# MCU.net
KiCad netlist of a schematic drawn in Altium Designer
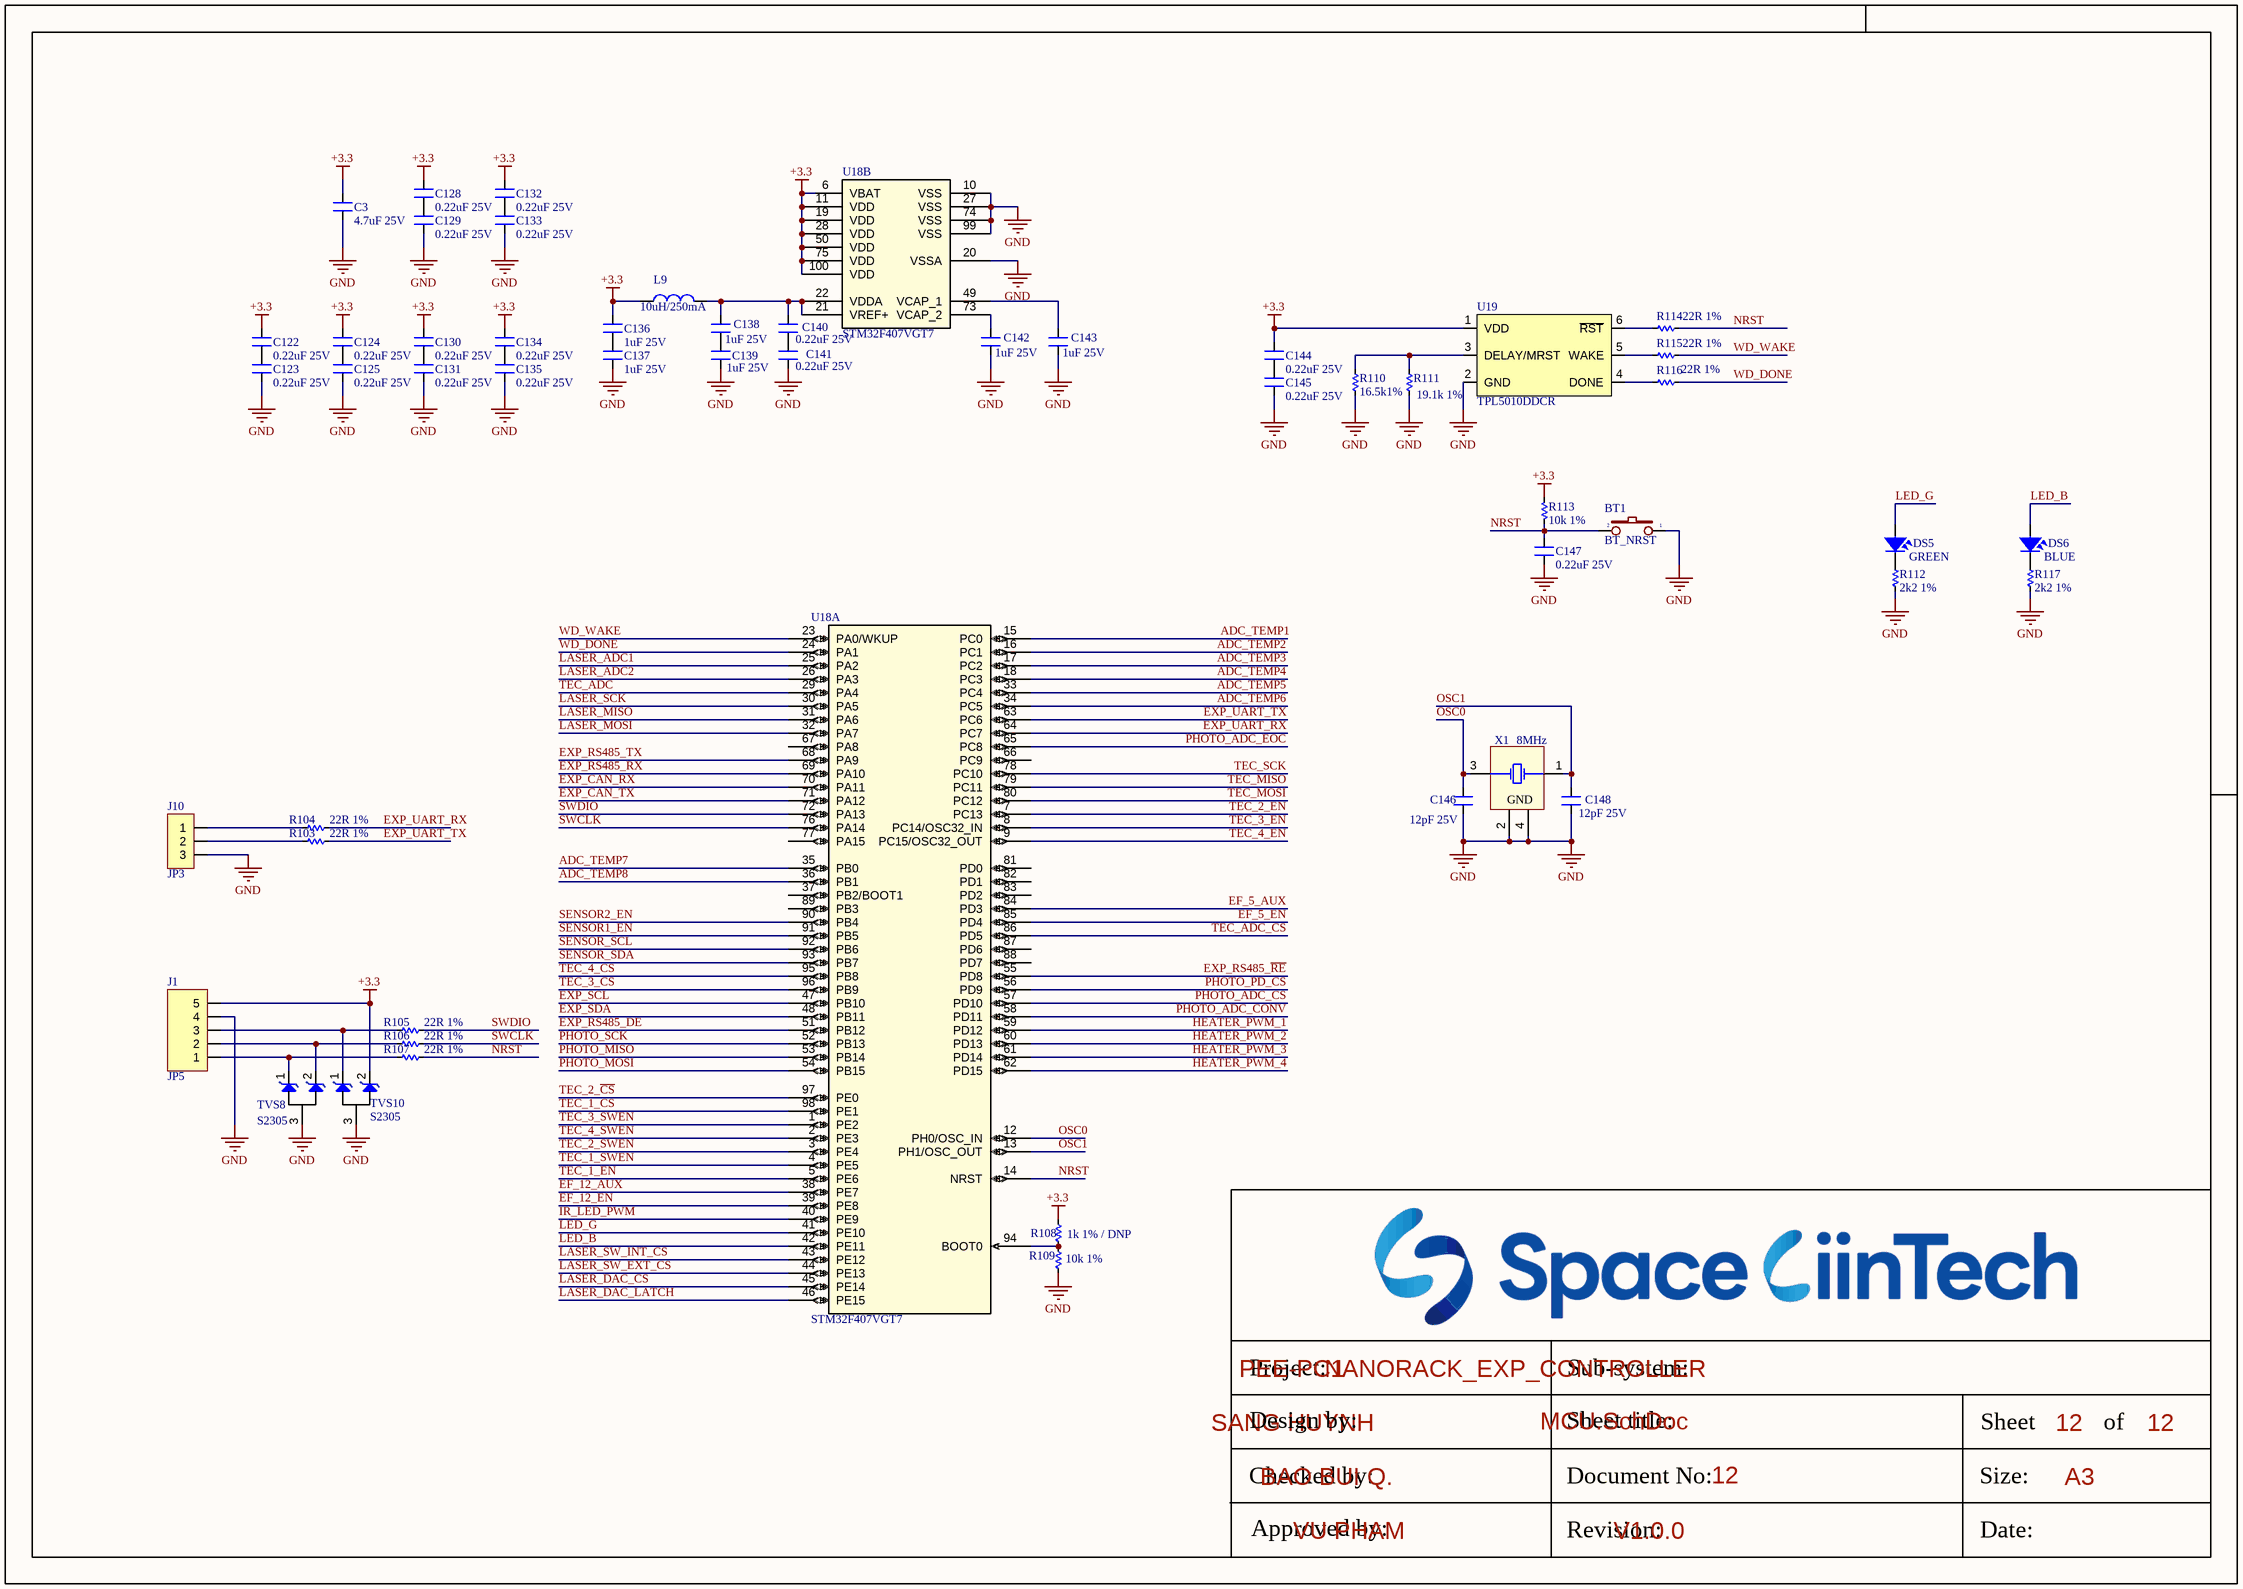
[diagram p0: MCU.SchDoc]

(export (version "E")
  (design (tool "Eeschema 10.0.6"))
  (components
    (comp (ref "BT1")
      (value "BT_NRST")
      (footprint "SW1-SMD")
      (description "Switch button 2 pin")
      (libsource (lib "Sang_library") (part "SW2"))
    )
    (comp (ref "C3")
      (value "4.7uF 25V")
      (footprint "CN-SMD-0603-EXP-V101")
      (libsource (lib "Sang_library") (part "Capacitors"))
    )
    (comp (ref "C122")
      (value "0.22uF 25V")
      (footprint "CN-SMD-0603-EXP-V101")
      (libsource (lib "Sang_library") (part "Capacitors"))
    )
    (comp (ref "C123")
      (value "0.22uF 25V")
      (footprint "CN-SMD-0603-EXP-V101")
      (libsource (lib "Sang_library") (part "Capacitors"))
    )
    (comp (ref "C124")
      (value "0.22uF 25V")
      (footprint "CN-SMD-0603-EXP-V101")
      (libsource (lib "Sang_library") (part "Capacitors"))
    )
    (comp (ref "C125")
      (value "0.22uF 25V")
      (footprint "CN-SMD-0603-EXP-V101")
      (libsource (lib "Sang_library") (part "Capacitors"))
    )
    (comp (ref "C128")
      (value "0.22uF 25V")
      (footprint "CN-SMD-0603-EXP-V101")
      (libsource (lib "Sang_library") (part "Capacitors"))
    )
    (comp (ref "C129")
      (value "0.22uF 25V")
      (footprint "CN-SMD-0603-EXP-V101")
      (libsource (lib "Sang_library") (part "Capacitors"))
    )
    (comp (ref "C130")
      (value "0.22uF 25V")
      (footprint "CN-SMD-0603-EXP-V101")
      (libsource (lib "Sang_library") (part "Capacitors"))
    )
    (comp (ref "C131")
      (value "0.22uF 25V")
      (footprint "CN-SMD-0603-EXP-V101")
      (libsource (lib "Sang_library") (part "Capacitors"))
    )
    (comp (ref "C132")
      (value "0.22uF 25V")
      (footprint "CN-SMD-0603-EXP-V101")
      (libsource (lib "Sang_library") (part "Capacitors"))
    )
    (comp (ref "C133")
      (value "0.22uF 25V")
      (footprint "CN-SMD-0603-EXP-V101")
      (libsource (lib "Sang_library") (part "Capacitors"))
    )
    (comp (ref "C134")
      (value "0.22uF 25V")
      (footprint "CN-SMD-0603-EXP-V101")
      (libsource (lib "Sang_library") (part "Capacitors"))
    )
    (comp (ref "C135")
      (value "0.22uF 25V")
      (footprint "CN-SMD-0603-EXP-V101")
      (libsource (lib "Sang_library") (part "Capacitors"))
    )
    (comp (ref "C136")
      (value "1uF 25V")
      (footprint "CN-SMD-0603-EXP-V101")
      (libsource (lib "Sang_library") (part "Capacitors"))
    )
    (comp (ref "C137")
      (value "1uF 25V")
      (footprint "CN-SMD-0603-EXP-V101")
      (libsource (lib "Sang_library") (part "Capacitors"))
    )
    (comp (ref "C138")
      (value "1uF 25V")
      (footprint "CN-SMD-0603-EXP-V101")
      (libsource (lib "Sang_library") (part "Capacitors"))
    )
    (comp (ref "C139")
      (value "1uF 25V")
      (footprint "CN-SMD-0603-EXP-V101")
      (libsource (lib "Sang_library") (part "Capacitors"))
    )
    (comp (ref "C140")
      (value "0.22uF 25V")
      (footprint "CN-SMD-0603-EXP-V101")
      (libsource (lib "Sang_library") (part "Capacitors"))
    )
    (comp (ref "C141")
      (value "0.22uF 25V")
      (footprint "CN-SMD-0603-EXP-V101")
      (libsource (lib "Sang_library") (part "Capacitors"))
    )
    (comp (ref "C142")
      (value "1uF 25V")
      (footprint "CN-SMD-0603-EXP-V101")
      (libsource (lib "Sang_library") (part "Capacitors"))
    )
    (comp (ref "C143")
      (value "1uF 25V")
      (footprint "CN-SMD-0603-EXP-V101")
      (libsource (lib "Sang_library") (part "Capacitors"))
    )
    (comp (ref "C144")
      (value "0.22uF 25V")
      (footprint "CN-SMD-0603-EXP-V101")
      (libsource (lib "Sang_library") (part "Capacitors"))
    )
    (comp (ref "C145")
      (value "0.22uF 25V")
      (footprint "CN-SMD-0603-EXP-V101")
      (libsource (lib "Sang_library") (part "Capacitors"))
    )
    (comp (ref "C146")
      (value "12pF 25V")
      (footprint "CN-SMD-0603-EXP-V101")
      (libsource (lib "Sang_library") (part "Capacitors"))
    )
    (comp (ref "C147")
      (value "0.22uF 25V")
      (footprint "CN-SMD-0603-EXP-V101")
      (libsource (lib "Sang_library") (part "Capacitors"))
    )
    (comp (ref "C148")
      (value "12pF 25V")
      (footprint "CN-SMD-0603-EXP-V101")
      (libsource (lib "Sang_library") (part "Capacitors"))
    )
    (comp (ref "DS5")
      (value "GREEN")
      (footprint "LED-0603-BLUE-EXP-V01")
      (libsource (lib "Sang_library") (part "LED SMD"))
    )
    (comp (ref "DS6")
      (value "BLUE")
      (footprint "LED-0603-BLUE-EXP-V01")
      (libsource (lib "Sang_library") (part "LED SMD"))
    )
    (comp (ref "J1")
      (value "JP5")
      (footprint "JP5-D1C")
      (description "WR-PHD 2.54 mm Angled Socket Header")
      (fields
        (field (name "MANUFACTURER") "Würth Elektronik eiSos GmbH")
        (field (name "PARTNO") "613005143121")
        (field (name "CREATED BY") "Karrer Zheng")
      )
      (libsource (lib "Sang_library") (part "JP5"))
    )
    (comp (ref "J10")
      (value "JP3")
      (footprint "JP3-D1C")
      (description "WR-PHD 2.54 mm Angled Socket Header")
      (fields
        (field (name "MANUFACTURER") "Würth Elektronik eiSos GmbH")
        (field (name "PARTNO") "613003143121")
        (field (name "CREATED BY") "Karrer Zheng")
      )
      (libsource (lib "Sang_library") (part "JP3"))
    )
    (comp (ref "L9")
      (value "10uH/250mA")
      (footprint "L-SMD-0603-EXP-V101")
      (fields
        (field (name "PARTNO") "78477010")
        (field (name "MANUFACTURER") "Wurth Elektronik")
        (field (name "CREATED BY") "Baojun Chen")
      )
      (libsource (lib "Sang_library") (part "L-SMD-1"))
    )
    (comp (ref "R103")
      (value "22R 1%")
      (footprint "RES-SMD-0603-EXP-V101")
      (description "SMD")
      (fields
        (field (name "MANUFACTURER") "Generic Components")
        (field (name "PUBLISHER") "Altium Hobart Technology Centre")
      )
      (libsource (lib "Sang_library") (part "Res SMD"))
    )
    (comp (ref "R104")
      (value "22R 1%")
      (footprint "RES-SMD-0603-EXP-V101")
      (description "SMD")
      (fields
        (field (name "MANUFACTURER") "Generic Components")
        (field (name "PUBLISHER") "Altium Hobart Technology Centre")
      )
      (libsource (lib "Sang_library") (part "Res SMD"))
    )
    (comp (ref "R105")
      (value "22R 1%")
      (footprint "RES-SMD-0603-EXP-V101")
      (description "SMD")
      (fields
        (field (name "MANUFACTURER") "Generic Components")
        (field (name "PUBLISHER") "Altium Hobart Technology Centre")
      )
      (libsource (lib "Sang_library") (part "Res SMD"))
    )
    (comp (ref "R106")
      (value "22R 1%")
      (footprint "RES-SMD-0603-EXP-V101")
      (description "SMD")
      (fields
        (field (name "MANUFACTURER") "Generic Components")
        (field (name "PUBLISHER") "Altium Hobart Technology Centre")
      )
      (libsource (lib "Sang_library") (part "Res SMD"))
    )
    (comp (ref "R107")
      (value "22R 1%")
      (footprint "RES-SMD-0603-EXP-V101")
      (description "SMD")
      (fields
        (field (name "MANUFACTURER") "Generic Components")
        (field (name "PUBLISHER") "Altium Hobart Technology Centre")
      )
      (libsource (lib "Sang_library") (part "Res SMD"))
    )
    (comp (ref "R108")
      (value "1k 1% / DNP")
      (footprint "RES-SMD-0603-EXP-V101")
      (description "SMD")
      (fields
        (field (name "MANUFACTURER") "Generic Components")
        (field (name "PUBLISHER") "Altium Hobart Technology Centre")
      )
      (libsource (lib "Sang_library") (part "Res SMD"))
    )
    (comp (ref "R109")
      (value "10k 1%")
      (footprint "RES-SMD-0603-EXP-V101")
      (description "SMD")
      (fields
        (field (name "MANUFACTURER") "Generic Components")
        (field (name "PUBLISHER") "Altium Hobart Technology Centre")
      )
      (libsource (lib "Sang_library") (part "Res SMD"))
    )
    (comp (ref "R110")
      (value "16.5k1%")
      (footprint "RES-SMD-0603-EXP-V101")
      (description "SMD")
      (fields
        (field (name "MANUFACTURER") "Generic Components")
        (field (name "PUBLISHER") "Altium Hobart Technology Centre")
      )
      (libsource (lib "Sang_library") (part "Res SMD"))
    )
    (comp (ref "R111")
      (value "19.1k 1%")
      (footprint "RES-SMD-0603-EXP-V101")
      (description "SMD")
      (fields
        (field (name "MANUFACTURER") "Generic Components")
        (field (name "PUBLISHER") "Altium Hobart Technology Centre")
      )
      (libsource (lib "Sang_library") (part "Res SMD"))
    )
    (comp (ref "R112")
      (value "2k2 1%")
      (footprint "RES-SMD-0603-EXP-V101")
      (description "SMD")
      (fields
        (field (name "MANUFACTURER") "Generic Components")
        (field (name "PUBLISHER") "Altium Hobart Technology Centre")
      )
      (libsource (lib "Sang_library") (part "Res SMD"))
    )
    (comp (ref "R113")
      (value "10k 1%")
      (footprint "RES-SMD-0603-EXP-V101")
      (description "SMD")
      (fields
        (field (name "MANUFACTURER") "Generic Components")
        (field (name "PUBLISHER") "Altium Hobart Technology Centre")
      )
      (libsource (lib "Sang_library") (part "Res SMD"))
    )
    (comp (ref "R114")
      (value "22R 1%")
      (footprint "RES-SMD-0603-EXP-V101")
      (description "SMD")
      (fields
        (field (name "MANUFACTURER") "Generic Components")
        (field (name "PUBLISHER") "Altium Hobart Technology Centre")
      )
      (libsource (lib "Sang_library") (part "Res SMD"))
    )
    (comp (ref "R115")
      (value "22R 1%")
      (footprint "RES-SMD-0603-EXP-V101")
      (description "SMD")
      (fields
        (field (name "MANUFACTURER") "Generic Components")
        (field (name "PUBLISHER") "Altium Hobart Technology Centre")
      )
      (libsource (lib "Sang_library") (part "Res SMD"))
    )
    (comp (ref "R116")
      (value "22R 1%")
      (footprint "RES-SMD-0603-EXP-V101")
      (description "SMD")
      (fields
        (field (name "MANUFACTURER") "Generic Components")
        (field (name "PUBLISHER") "Altium Hobart Technology Centre")
      )
      (libsource (lib "Sang_library") (part "Res SMD"))
    )
    (comp (ref "R117")
      (value "2k2 1%")
      (footprint "RES-SMD-0603-EXP-V101")
      (description "SMD")
      (fields
        (field (name "MANUFACTURER") "Generic Components")
        (field (name "PUBLISHER") "Altium Hobart Technology Centre")
      )
      (libsource (lib "Sang_library") (part "Res SMD"))
    )
    (comp (ref "TVS8")
      (value "S2305")
      (footprint "sot23-12_3")
      (description "TVS DIODE 5VWM 10.8VC SOT23")
      (libsource (lib "Sang_library") (part "S2305"))
    )
    (comp (ref "TVS10")
      (value "S2305")
      (footprint "sot23-12_3")
      (description "TVS DIODE 5VWM 10.8VC SOT23")
      (libsource (lib "Sang_library") (part "S2305"))
    )
    (comp (ref "U18")
      (value "STM32F407VGT7")
      (footprint "LQFP-100")
      (libsource (lib "Sang_library") (part "STM32F407VGT7"))
    )
    (comp (ref "U19")
      (value "TPL5010DDCR")
      (footprint "SOT23-6-123_456")
      (description "IC OSC PROG TIMER TSOT23-6")
      (libsource (lib "Sang_library") (part "TPL5010DDCR"))
    )
    (comp (ref "X1")
      (value "8MHz")
      (footprint "XT4-16.000MHz-4_V")
      (description "Crystal, 8 MHz, -30 to 85 degC, 3.2 x 2.5 x 0.9 mm SMD")
      (libsource (lib "Library") (part "XT4"))
    )
  )
  (nets
    (net (code "1") (name "+3.3") (class "Default")
      (node (ref "C122") (pin "2") (pinfunction "2_2") (pintype "passive"))
      (node (ref "C124") (pin "2") (pinfunction "2_2") (pintype "passive"))
      (node (ref "C128") (pin "2") (pinfunction "2_2") (pintype "passive"))
      (node (ref "C130") (pin "2") (pinfunction "2_2") (pintype "passive"))
      (node (ref "C132") (pin "2") (pinfunction "2_2") (pintype "passive"))
      (node (ref "C134") (pin "2") (pinfunction "2_2") (pintype "passive"))
      (node (ref "C136") (pin "2") (pinfunction "2_2") (pintype "passive"))
      (node (ref "C144") (pin "2") (pinfunction "2_2") (pintype "passive"))
      (node (ref "C3") (pin "2") (pinfunction "2_2") (pintype "passive"))
      (node (ref "J1") (pin "5") (pinfunction "5_5") (pintype "passive"))
      (node (ref "L9") (pin "1") (pinfunction "1_1") (pintype "passive"))
      (node (ref "R108") (pin "1") (pinfunction "1_1") (pintype "passive"))
      (node (ref "R113") (pin "1") (pinfunction "1_1") (pintype "passive"))
      (node (ref "TVS10") (pin "2") (pinfunction "2_2") (pintype "passive"))
      (node (ref "U18") (pin "100") (pinfunction "VDD_100") (pintype "power_in"))
      (node (ref "U18") (pin "11") (pinfunction "VDD_11") (pintype "power_in"))
      (node (ref "U18") (pin "19") (pinfunction "VDD_19") (pintype "power_in"))
      (node (ref "U18") (pin "28") (pinfunction "VDD_28") (pintype "power_in"))
      (node (ref "U18") (pin "50") (pinfunction "VDD_50") (pintype "power_in"))
      (node (ref "U18") (pin "6") (pinfunction "VBAT_6") (pintype "power_in"))
      (node (ref "U18") (pin "75") (pinfunction "VDD_75") (pintype "power_in"))
      (node (ref "U19") (pin "1") (pinfunction "VDD_1") (pintype "passive"))
    )
    (net (code "2") (name "/ADC_TEMP1") (class "Default")
      (node (ref "U18") (pin "15") (pinfunction "PC0_15") (pintype "bidirectional"))
    )
    (net (code "3") (name "/ADC_TEMP2") (class "Default")
      (node (ref "U18") (pin "16") (pinfunction "PC1_16") (pintype "bidirectional"))
    )
    (net (code "4") (name "/ADC_TEMP3") (class "Default")
      (node (ref "U18") (pin "17") (pinfunction "PC2_17") (pintype "bidirectional"))
    )
    (net (code "5") (name "/ADC_TEMP4") (class "Default")
      (node (ref "U18") (pin "18") (pinfunction "PC3_18") (pintype "bidirectional"))
    )
    (net (code "6") (name "/ADC_TEMP5") (class "Default")
      (node (ref "U18") (pin "33") (pinfunction "PC4_33") (pintype "bidirectional"))
    )
    (net (code "7") (name "/ADC_TEMP6") (class "Default")
      (node (ref "U18") (pin "34") (pinfunction "PC5_34") (pintype "bidirectional"))
    )
    (net (code "8") (name "/ADC_TEMP7") (class "Default")
      (node (ref "U18") (pin "35") (pinfunction "PB0_35") (pintype "bidirectional"))
    )
    (net (code "9") (name "/ADC_TEMP8") (class "Default")
      (node (ref "U18") (pin "36") (pinfunction "PB1_36") (pintype "bidirectional"))
    )
    (net (code "10") (name "/EF_5_AUX") (class "Default")
      (node (ref "U18") (pin "84") (pinfunction "PD3_84") (pintype "bidirectional"))
    )
    (net (code "11") (name "/EF_5_EN") (class "Default")
      (node (ref "U18") (pin "85") (pinfunction "PD4_85") (pintype "bidirectional"))
    )
    (net (code "12") (name "/EF_12_AUX") (class "Default")
      (node (ref "U18") (pin "38") (pinfunction "PE7_38") (pintype "bidirectional"))
    )
    (net (code "13") (name "/EF_12_EN") (class "Default")
      (node (ref "U18") (pin "39") (pinfunction "PE8_39") (pintype "bidirectional"))
    )
    (net (code "14") (name "/EXP_CAN_RX") (class "Default")
      (node (ref "U18") (pin "70") (pinfunction "PA11_70") (pintype "bidirectional"))
    )
    (net (code "15") (name "/EXP_CAN_TX") (class "Default")
      (node (ref "U18") (pin "71") (pinfunction "PA12_71") (pintype "bidirectional"))
    )
    (net (code "16") (name "/EXP_RS485_DE") (class "Default")
      (node (ref "U18") (pin "51") (pinfunction "PB12_51") (pintype "bidirectional"))
    )
    (net (code "17") (name "/EXP_RS485_RX") (class "Default")
      (node (ref "U18") (pin "69") (pinfunction "PA10_69") (pintype "bidirectional"))
    )
    (net (code "18") (name "/EXP_RS485_TX") (class "Default")
      (node (ref "U18") (pin "68") (pinfunction "PA9_68") (pintype "bidirectional"))
    )
    (net (code "19") (name "/EXP_RS485_~{RE}") (class "Default")
      (node (ref "U18") (pin "55") (pinfunction "PD8_55") (pintype "bidirectional"))
    )
    (net (code "20") (name "/EXP_SCL") (class "Default")
      (node (ref "U18") (pin "47") (pinfunction "PB10_47") (pintype "bidirectional"))
    )
    (net (code "21") (name "/EXP_SDA") (class "Default")
      (node (ref "U18") (pin "48") (pinfunction "PB11_48") (pintype "bidirectional"))
    )
    (net (code "22") (name "/EXP_UART_RX") (class "Default")
      (node (ref "R104") (pin "1") (pinfunction "1_1") (pintype "passive"))
      (node (ref "U18") (pin "64") (pinfunction "PC7_64") (pintype "bidirectional"))
    )
    (net (code "23") (name "/EXP_UART_TX") (class "Default")
      (node (ref "R103") (pin "1") (pinfunction "1_1") (pintype "passive"))
      (node (ref "U18") (pin "63") (pinfunction "PC6_63") (pintype "bidirectional"))
    )
    (net (code "24") (name "/HEATER_PWM_1") (class "Default")
      (node (ref "U18") (pin "59") (pinfunction "PD12_59") (pintype "bidirectional"))
    )
    (net (code "25") (name "/HEATER_PWM_2") (class "Default")
      (node (ref "U18") (pin "60") (pinfunction "PD13_60") (pintype "bidirectional"))
    )
    (net (code "26") (name "/HEATER_PWM_3") (class "Default")
      (node (ref "U18") (pin "61") (pinfunction "PD14_61") (pintype "bidirectional"))
    )
    (net (code "27") (name "/HEATER_PWM_4") (class "Default")
      (node (ref "U18") (pin "62") (pinfunction "PD15_62") (pintype "bidirectional"))
    )
    (net (code "28") (name "/IR_LED_PWM") (class "Default")
      (node (ref "U18") (pin "40") (pinfunction "PE9_40") (pintype "bidirectional"))
    )
    (net (code "29") (name "/LASER_ADC1") (class "Default")
      (node (ref "U18") (pin "25") (pinfunction "PA2_25") (pintype "bidirectional"))
    )
    (net (code "30") (name "/LASER_ADC2") (class "Default")
      (node (ref "U18") (pin "26") (pinfunction "PA3_26") (pintype "bidirectional"))
    )
    (net (code "31") (name "/LASER_DAC_CS") (class "Default")
      (node (ref "U18") (pin "45") (pinfunction "PE14_45") (pintype "bidirectional"))
    )
    (net (code "32") (name "/LASER_DAC_LATCH") (class "Default")
      (node (ref "U18") (pin "46") (pinfunction "PE15_46") (pintype "bidirectional"))
    )
    (net (code "33") (name "/LASER_MISO") (class "Default")
      (node (ref "U18") (pin "31") (pinfunction "PA6_31") (pintype "bidirectional"))
    )
    (net (code "34") (name "/LASER_MOSI") (class "Default")
      (node (ref "U18") (pin "32") (pinfunction "PA7_32") (pintype "bidirectional"))
    )
    (net (code "35") (name "/LASER_SCK") (class "Default")
      (node (ref "U18") (pin "30") (pinfunction "PA5_30") (pintype "bidirectional"))
    )
    (net (code "36") (name "/LASER_SW_EXT_CS") (class "Default")
      (node (ref "U18") (pin "44") (pinfunction "PE13_44") (pintype "bidirectional"))
    )
    (net (code "37") (name "/LASER_SW_INT_CS") (class "Default")
      (node (ref "U18") (pin "43") (pinfunction "PE12_43") (pintype "bidirectional"))
    )
    (net (code "38") (name "/LED_B") (class "Default")
      (node (ref "DS6") (pin "1") (pinfunction "1_1") (pintype "passive"))
      (node (ref "U18") (pin "42") (pinfunction "PE11_42") (pintype "bidirectional"))
    )
    (net (code "39") (name "/LED_G") (class "Default")
      (node (ref "DS5") (pin "1") (pinfunction "1_1") (pintype "passive"))
      (node (ref "U18") (pin "41") (pinfunction "PE10_41") (pintype "bidirectional"))
    )
    (net (code "40") (name "/NRST") (class "Default")
      (node (ref "BT1") (pin "2") (pinfunction "2_2") (pintype "passive"))
      (node (ref "C147") (pin "2") (pinfunction "2_2") (pintype "passive"))
      (node (ref "R107") (pin "1") (pinfunction "1_1") (pintype "passive"))
      (node (ref "R113") (pin "2") (pinfunction "2_2") (pintype "passive"))
      (node (ref "R114") (pin "2") (pinfunction "2_2") (pintype "passive"))
      (node (ref "U18") (pin "14") (pinfunction "NRST_14") (pintype "bidirectional"))
    )
    (net (code "41") (name "/OSC0") (class "Default")
      (node (ref "C146") (pin "1") (pinfunction "1_1") (pintype "passive"))
      (node (ref "U18") (pin "12") (pinfunction "PH0/OSC_IN_12") (pintype "bidirectional"))
      (node (ref "X1") (pin "3") (pinfunction "XTAL_3") (pintype "passive"))
    )
    (net (code "42") (name "/OSC1") (class "Default")
      (node (ref "C148") (pin "2") (pinfunction "2_2") (pintype "passive"))
      (node (ref "U18") (pin "13") (pinfunction "PH1/OSC_OUT_13") (pintype "bidirectional"))
      (node (ref "X1") (pin "1") (pinfunction "XTAL_1") (pintype "passive"))
    )
    (net (code "43") (name "/PHOTO_ADC_CONV") (class "Default")
      (node (ref "U18") (pin "58") (pinfunction "PD11_58") (pintype "bidirectional"))
    )
    (net (code "44") (name "/PHOTO_ADC_CS") (class "Default")
      (node (ref "U18") (pin "57") (pinfunction "PD10_57") (pintype "bidirectional"))
    )
    (net (code "45") (name "/PHOTO_ADC_EOC") (class "Default")
      (node (ref "U18") (pin "65") (pinfunction "PC8_65") (pintype "bidirectional"))
    )
    (net (code "46") (name "/PHOTO_MISO") (class "Default")
      (node (ref "U18") (pin "53") (pinfunction "PB14_53") (pintype "bidirectional"))
    )
    (net (code "47") (name "/PHOTO_MOSI") (class "Default")
      (node (ref "U18") (pin "54") (pinfunction "PB15_54") (pintype "bidirectional"))
    )
    (net (code "48") (name "/PHOTO_PD_CS") (class "Default")
      (node (ref "U18") (pin "56") (pinfunction "PD9_56") (pintype "bidirectional"))
    )
    (net (code "49") (name "/PHOTO_SCK") (class "Default")
      (node (ref "U18") (pin "52") (pinfunction "PB13_52") (pintype "bidirectional"))
    )
    (net (code "50") (name "/SENSOR1_EN") (class "Default")
      (node (ref "U18") (pin "91") (pinfunction "PB5_91") (pintype "bidirectional"))
    )
    (net (code "51") (name "/SENSOR2_EN") (class "Default")
      (node (ref "U18") (pin "90") (pinfunction "PB4_90") (pintype "bidirectional"))
    )
    (net (code "52") (name "/SENSOR_SCL") (class "Default")
      (node (ref "U18") (pin "92") (pinfunction "PB6_92") (pintype "bidirectional"))
    )
    (net (code "53") (name "/SENSOR_SDA") (class "Default")
      (node (ref "U18") (pin "93") (pinfunction "PB7_93") (pintype "bidirectional"))
    )
    (net (code "54") (name "/SWCLK") (class "Default")
      (node (ref "R106") (pin "1") (pinfunction "1_1") (pintype "passive"))
      (node (ref "U18") (pin "76") (pinfunction "PA14_76") (pintype "bidirectional"))
    )
    (net (code "55") (name "/SWDIO") (class "Default")
      (node (ref "R105") (pin "1") (pinfunction "1_1") (pintype "passive"))
      (node (ref "U18") (pin "72") (pinfunction "PA13_72") (pintype "bidirectional"))
    )
    (net (code "56") (name "/TEC_1_EN") (class "Default")
      (node (ref "U18") (pin "5") (pinfunction "PE6_5") (pintype "bidirectional"))
    )
    (net (code "57") (name "/TEC_1_SWEN") (class "Default")
      (node (ref "U18") (pin "4") (pinfunction "PE5_4") (pintype "bidirectional"))
    )
    (net (code "58") (name "/TEC_1_~{CS}") (class "Default")
      (node (ref "U18") (pin "98") (pinfunction "PE1_98") (pintype "bidirectional"))
    )
    (net (code "59") (name "/TEC_2_EN") (class "Default")
      (node (ref "U18") (pin "7") (pinfunction "PC13_7") (pintype "bidirectional"))
    )
    (net (code "60") (name "/TEC_2_SWEN") (class "Default")
      (node (ref "U18") (pin "3") (pinfunction "PE4_3") (pintype "bidirectional"))
    )
    (net (code "61") (name "/TEC_2_~{CS}") (class "Default")
      (node (ref "U18") (pin "97") (pinfunction "PE0_97") (pintype "bidirectional"))
    )
    (net (code "62") (name "/TEC_3_EN") (class "Default")
      (node (ref "U18") (pin "8") (pinfunction "PC14/OSC32_IN_8") (pintype "bidirectional"))
    )
    (net (code "63") (name "/TEC_3_SWEN") (class "Default")
      (node (ref "U18") (pin "1") (pinfunction "PE2_1") (pintype "bidirectional"))
    )
    (net (code "64") (name "/TEC_3_~{CS}") (class "Default")
      (node (ref "U18") (pin "96") (pinfunction "PB9_96") (pintype "bidirectional"))
    )
    (net (code "65") (name "/TEC_4_EN") (class "Default")
      (node (ref "U18") (pin "9") (pinfunction "PC15/OSC32_OUT_9") (pintype "bidirectional"))
    )
    (net (code "66") (name "/TEC_4_SWEN") (class "Default")
      (node (ref "U18") (pin "2") (pinfunction "PE3_2") (pintype "bidirectional"))
    )
    (net (code "67") (name "/TEC_4_~{CS}") (class "Default")
      (node (ref "U18") (pin "95") (pinfunction "PB8_95") (pintype "bidirectional"))
    )
    (net (code "68") (name "/TEC_ADC") (class "Default")
      (node (ref "U18") (pin "29") (pinfunction "PA4_29") (pintype "bidirectional"))
    )
    (net (code "69") (name "/TEC_ADC_~{CS}") (class "Default")
      (node (ref "U18") (pin "86") (pinfunction "PD5_86") (pintype "bidirectional"))
    )
    (net (code "70") (name "/TEC_MISO") (class "Default")
      (node (ref "U18") (pin "79") (pinfunction "PC11_79") (pintype "bidirectional"))
    )
    (net (code "71") (name "/TEC_MOSI") (class "Default")
      (node (ref "U18") (pin "80") (pinfunction "PC12_80") (pintype "bidirectional"))
    )
    (net (code "72") (name "/TEC_SCK") (class "Default")
      (node (ref "U18") (pin "78") (pinfunction "PC10_78") (pintype "bidirectional"))
    )
    (net (code "73") (name "/WD_DONE") (class "Default")
      (node (ref "R116") (pin "2") (pinfunction "2_2") (pintype "passive"))
      (node (ref "U18") (pin "24") (pinfunction "PA1_24") (pintype "bidirectional"))
    )
    (net (code "74") (name "/WD_WAKE") (class "Default")
      (node (ref "R115") (pin "2") (pinfunction "2_2") (pintype "passive"))
      (node (ref "U18") (pin "23") (pinfunction "PA0/WKUP_23") (pintype "bidirectional"))
    )
    (net (code "75") (name "GND") (class "Default")
      (node (ref "BT1") (pin "1") (pinfunction "1_1") (pintype "passive"))
      (node (ref "C123") (pin "1") (pinfunction "1_1") (pintype "passive"))
      (node (ref "C125") (pin "1") (pinfunction "1_1") (pintype "passive"))
      (node (ref "C129") (pin "1") (pinfunction "1_1") (pintype "passive"))
      (node (ref "C131") (pin "1") (pinfunction "1_1") (pintype "passive"))
      (node (ref "C133") (pin "1") (pinfunction "1_1") (pintype "passive"))
      (node (ref "C135") (pin "1") (pinfunction "1_1") (pintype "passive"))
      (node (ref "C137") (pin "1") (pinfunction "1_1") (pintype "passive"))
      (node (ref "C139") (pin "1") (pinfunction "1_1") (pintype "passive"))
      (node (ref "C141") (pin "1") (pinfunction "1_1") (pintype "passive"))
      (node (ref "C142") (pin "1") (pinfunction "1_1") (pintype "passive"))
      (node (ref "C143") (pin "1") (pinfunction "1_1") (pintype "passive"))
      (node (ref "C145") (pin "1") (pinfunction "1_1") (pintype "passive"))
      (node (ref "C146") (pin "2") (pinfunction "2_2") (pintype "passive"))
      (node (ref "C147") (pin "1") (pinfunction "1_1") (pintype "passive"))
      (node (ref "C148") (pin "1") (pinfunction "1_1") (pintype "passive"))
      (node (ref "C3") (pin "1") (pinfunction "1_1") (pintype "passive"))
      (node (ref "J1") (pin "4") (pinfunction "4_4") (pintype "passive"))
      (node (ref "J10") (pin "3") (pinfunction "3_3") (pintype "passive"))
      (node (ref "R109") (pin "2") (pinfunction "2_2") (pintype "passive"))
      (node (ref "R110") (pin "1") (pinfunction "1_1") (pintype "passive"))
      (node (ref "R111") (pin "1") (pinfunction "1_1") (pintype "passive"))
      (node (ref "R112") (pin "2") (pinfunction "2_2") (pintype "passive"))
      (node (ref "R117") (pin "2") (pinfunction "2_2") (pintype "passive"))
      (node (ref "TVS10") (pin "3") (pinfunction "3_3") (pintype "passive"))
      (node (ref "TVS8") (pin "3") (pinfunction "3_3") (pintype "passive"))
      (node (ref "U18") (pin "10") (pinfunction "VSS_10") (pintype "power_in"))
      (node (ref "U18") (pin "20") (pinfunction "VSSA_20") (pintype "power_in"))
      (node (ref "U18") (pin "27") (pinfunction "VSS_27") (pintype "power_in"))
      (node (ref "U18") (pin "74") (pinfunction "VSS_74") (pintype "power_in"))
      (node (ref "U18") (pin "99") (pinfunction "VSS_99") (pintype "power_in"))
      (node (ref "U19") (pin "2") (pinfunction "GND_2") (pintype "passive"))
      (node (ref "X1") (pin "2") (pinfunction "GND_2") (pintype "power_in"))
      (node (ref "X1") (pin "4") (pinfunction "GND_4") (pintype "power_in"))
    )
    (net (code "76") (name "Net-(C122-Pad1)") (class "Default")
      (node (ref "C122") (pin "1") (pinfunction "1_1") (pintype "passive"))
      (node (ref "C123") (pin "2") (pinfunction "2_2") (pintype "passive"))
    )
    (net (code "77") (name "Net-(C124-Pad1)") (class "Default")
      (node (ref "C124") (pin "1") (pinfunction "1_1") (pintype "passive"))
      (node (ref "C125") (pin "2") (pinfunction "2_2") (pintype "passive"))
    )
    (net (code "78") (name "Net-(C128-Pad1)") (class "Default")
      (node (ref "C128") (pin "1") (pinfunction "1_1") (pintype "passive"))
      (node (ref "C129") (pin "2") (pinfunction "2_2") (pintype "passive"))
    )
    (net (code "79") (name "Net-(C130-Pad1)") (class "Default")
      (node (ref "C130") (pin "1") (pinfunction "1_1") (pintype "passive"))
      (node (ref "C131") (pin "2") (pinfunction "2_2") (pintype "passive"))
    )
    (net (code "80") (name "Net-(C132-Pad1)") (class "Default")
      (node (ref "C132") (pin "1") (pinfunction "1_1") (pintype "passive"))
      (node (ref "C133") (pin "2") (pinfunction "2_2") (pintype "passive"))
    )
    (net (code "81") (name "Net-(C134-Pad1)") (class "Default")
      (node (ref "C134") (pin "1") (pinfunction "1_1") (pintype "passive"))
      (node (ref "C135") (pin "2") (pinfunction "2_2") (pintype "passive"))
    )
    (net (code "82") (name "Net-(C136-Pad1)") (class "Default")
      (node (ref "C136") (pin "1") (pinfunction "1_1") (pintype "passive"))
      (node (ref "C137") (pin "2") (pinfunction "2_2") (pintype "passive"))
    )
    (net (code "83") (name "Net-(C138-Pad1)") (class "Default")
      (node (ref "C138") (pin "1") (pinfunction "1_1") (pintype "passive"))
      (node (ref "C139") (pin "2") (pinfunction "2_2") (pintype "passive"))
    )
    (net (code "84") (name "Net-(C140-Pad1)") (class "Default")
      (node (ref "C140") (pin "1") (pinfunction "1_1") (pintype "passive"))
      (node (ref "C141") (pin "2") (pinfunction "2_2") (pintype "passive"))
    )
    (net (code "85") (name "Net-(C144-Pad1)") (class "Default")
      (node (ref "C144") (pin "1") (pinfunction "1_1") (pintype "passive"))
      (node (ref "C145") (pin "2") (pinfunction "2_2") (pintype "passive"))
    )
    (net (code "86") (name "Net-(DS5-Pad2)") (class "Default")
      (node (ref "DS5") (pin "2") (pinfunction "2_2") (pintype "passive"))
      (node (ref "R112") (pin "1") (pinfunction "1_1") (pintype "passive"))
    )
    (net (code "87") (name "Net-(DS6-Pad2)") (class "Default")
      (node (ref "DS6") (pin "2") (pinfunction "2_2") (pintype "passive"))
      (node (ref "R117") (pin "1") (pinfunction "1_1") (pintype "passive"))
    )
    (net (code "88") (name "Net-(J1-Pad1)") (class "Default")
      (node (ref "J1") (pin "1") (pinfunction "1_1") (pintype "passive"))
      (node (ref "R107") (pin "2") (pinfunction "2_2") (pintype "passive"))
      (node (ref "TVS8") (pin "1") (pinfunction "1_1") (pintype "passive"))
    )
    (net (code "89") (name "Net-(J1-Pad2)") (class "Default")
      (node (ref "J1") (pin "2") (pinfunction "2_2") (pintype "passive"))
      (node (ref "R106") (pin "2") (pinfunction "2_2") (pintype "passive"))
      (node (ref "TVS8") (pin "2") (pinfunction "2_2") (pintype "passive"))
    )
    (net (code "90") (name "Net-(J1-Pad3)") (class "Default")
      (node (ref "J1") (pin "3") (pinfunction "3_3") (pintype "passive"))
      (node (ref "R105") (pin "2") (pinfunction "2_2") (pintype "passive"))
      (node (ref "TVS10") (pin "1") (pinfunction "1_1") (pintype "passive"))
    )
    (net (code "91") (name "Net-(J10-Pad1)") (class "Default")
      (node (ref "J10") (pin "1") (pinfunction "1_1") (pintype "passive"))
      (node (ref "R104") (pin "2") (pinfunction "2_2") (pintype "passive"))
    )
    (net (code "92") (name "Net-(J10-Pad2)") (class "Default")
      (node (ref "J10") (pin "2") (pinfunction "2_2") (pintype "passive"))
      (node (ref "R103") (pin "2") (pinfunction "2_2") (pintype "passive"))
    )
    (net (code "93") (name "Net-(U18A-BOOT0)") (class "Default")
      (node (ref "R108") (pin "2") (pinfunction "2_2") (pintype "passive"))
      (node (ref "R109") (pin "1") (pinfunction "1_1") (pintype "passive"))
      (node (ref "U18") (pin "94") (pinfunction "BOOT0_94") (pintype "input"))
    )
    (net (code "94") (name "Net-(U18B-VCAP_1)") (class "Default")
      (node (ref "C143") (pin "2") (pinfunction "2_2") (pintype "passive"))
      (node (ref "U18") (pin "49") (pinfunction "VCAP_1_49") (pintype "power_in"))
    )
    (net (code "95") (name "Net-(U18B-VCAP_2)") (class "Default")
      (node (ref "C142") (pin "2") (pinfunction "2_2") (pintype "passive"))
      (node (ref "U18") (pin "73") (pinfunction "VCAP_2_73") (pintype "power_in"))
    )
    (net (code "96") (name "Net-(U18B-VDDA)") (class "Default")
      (node (ref "C138") (pin "2") (pinfunction "2_2") (pintype "passive"))
      (node (ref "C140") (pin "2") (pinfunction "2_2") (pintype "passive"))
      (node (ref "L9") (pin "2") (pinfunction "2_2") (pintype "passive"))
      (node (ref "U18") (pin "21") (pinfunction "VREF+_21") (pintype "power_in"))
      (node (ref "U18") (pin "22") (pinfunction "VDDA_22") (pintype "power_in"))
    )
    (net (code "97") (name "Net-(U19-DELAY{slash}MRST)") (class "Default")
      (node (ref "R110") (pin "2") (pinfunction "2_2") (pintype "passive"))
      (node (ref "R111") (pin "2") (pinfunction "2_2") (pintype "passive"))
      (node (ref "U19") (pin "3") (pinfunction "DELAY/MRST_3") (pintype "passive"))
    )
    (net (code "98") (name "Net-(U19-DONE)") (class "Default")
      (node (ref "R116") (pin "1") (pinfunction "1_1") (pintype "passive"))
      (node (ref "U19") (pin "4") (pinfunction "DONE_4") (pintype "passive"))
    )
    (net (code "99") (name "Net-(U19-WAKE)") (class "Default")
      (node (ref "R115") (pin "1") (pinfunction "1_1") (pintype "passive"))
      (node (ref "U19") (pin "5") (pinfunction "WAKE_5") (pintype "passive"))
    )
    (net (code "100") (name "Net-(U19-~{RST})") (class "Default")
      (node (ref "R114") (pin "1") (pinfunction "1_1") (pintype "passive"))
      (node (ref "U19") (pin "6") (pinfunction "~{RST}_6") (pintype "passive"))
    )
    (net (code "101") (name "unconnected-(U18A-PA8-Pad67)") (class "Default")
      (node (ref "U18") (pin "67") (pinfunction "PA8_67") (pintype "bidirectional"))
    )
    (net (code "102") (name "unconnected-(U18A-PA15-Pad77)") (class "Default")
      (node (ref "U18") (pin "77") (pinfunction "PA15_77") (pintype "bidirectional"))
    )
    (net (code "103") (name "unconnected-(U18A-PB2{slash}BOOT1-Pad37)") (class "Default")
      (node (ref "U18") (pin "37") (pinfunction "PB2/BOOT1_37") (pintype "bidirectional"))
    )
    (net (code "104") (name "unconnected-(U18A-PB3-Pad89)") (class "Default")
      (node (ref "U18") (pin "89") (pinfunction "PB3_89") (pintype "bidirectional"))
    )
    (net (code "105") (name "unconnected-(U18A-PC9-Pad66)") (class "Default")
      (node (ref "U18") (pin "66") (pinfunction "PC9_66") (pintype "bidirectional"))
    )
    (net (code "106") (name "unconnected-(U18A-PD0-Pad81)") (class "Default")
      (node (ref "U18") (pin "81") (pinfunction "PD0_81") (pintype "bidirectional"))
    )
    (net (code "107") (name "unconnected-(U18A-PD1-Pad82)") (class "Default")
      (node (ref "U18") (pin "82") (pinfunction "PD1_82") (pintype "bidirectional"))
    )
    (net (code "108") (name "unconnected-(U18A-PD2-Pad83)") (class "Default")
      (node (ref "U18") (pin "83") (pinfunction "PD2_83") (pintype "bidirectional"))
    )
    (net (code "109") (name "unconnected-(U18A-PD6-Pad87)") (class "Default")
      (node (ref "U18") (pin "87") (pinfunction "PD6_87") (pintype "bidirectional"))
    )
    (net (code "110") (name "unconnected-(U18A-PD7-Pad88)") (class "Default")
      (node (ref "U18") (pin "88") (pinfunction "PD7_88") (pintype "bidirectional"))
    )
  )
)
